# CurrentStabilizer.net
KiCad netlist of a schematic drawn in EAGLE
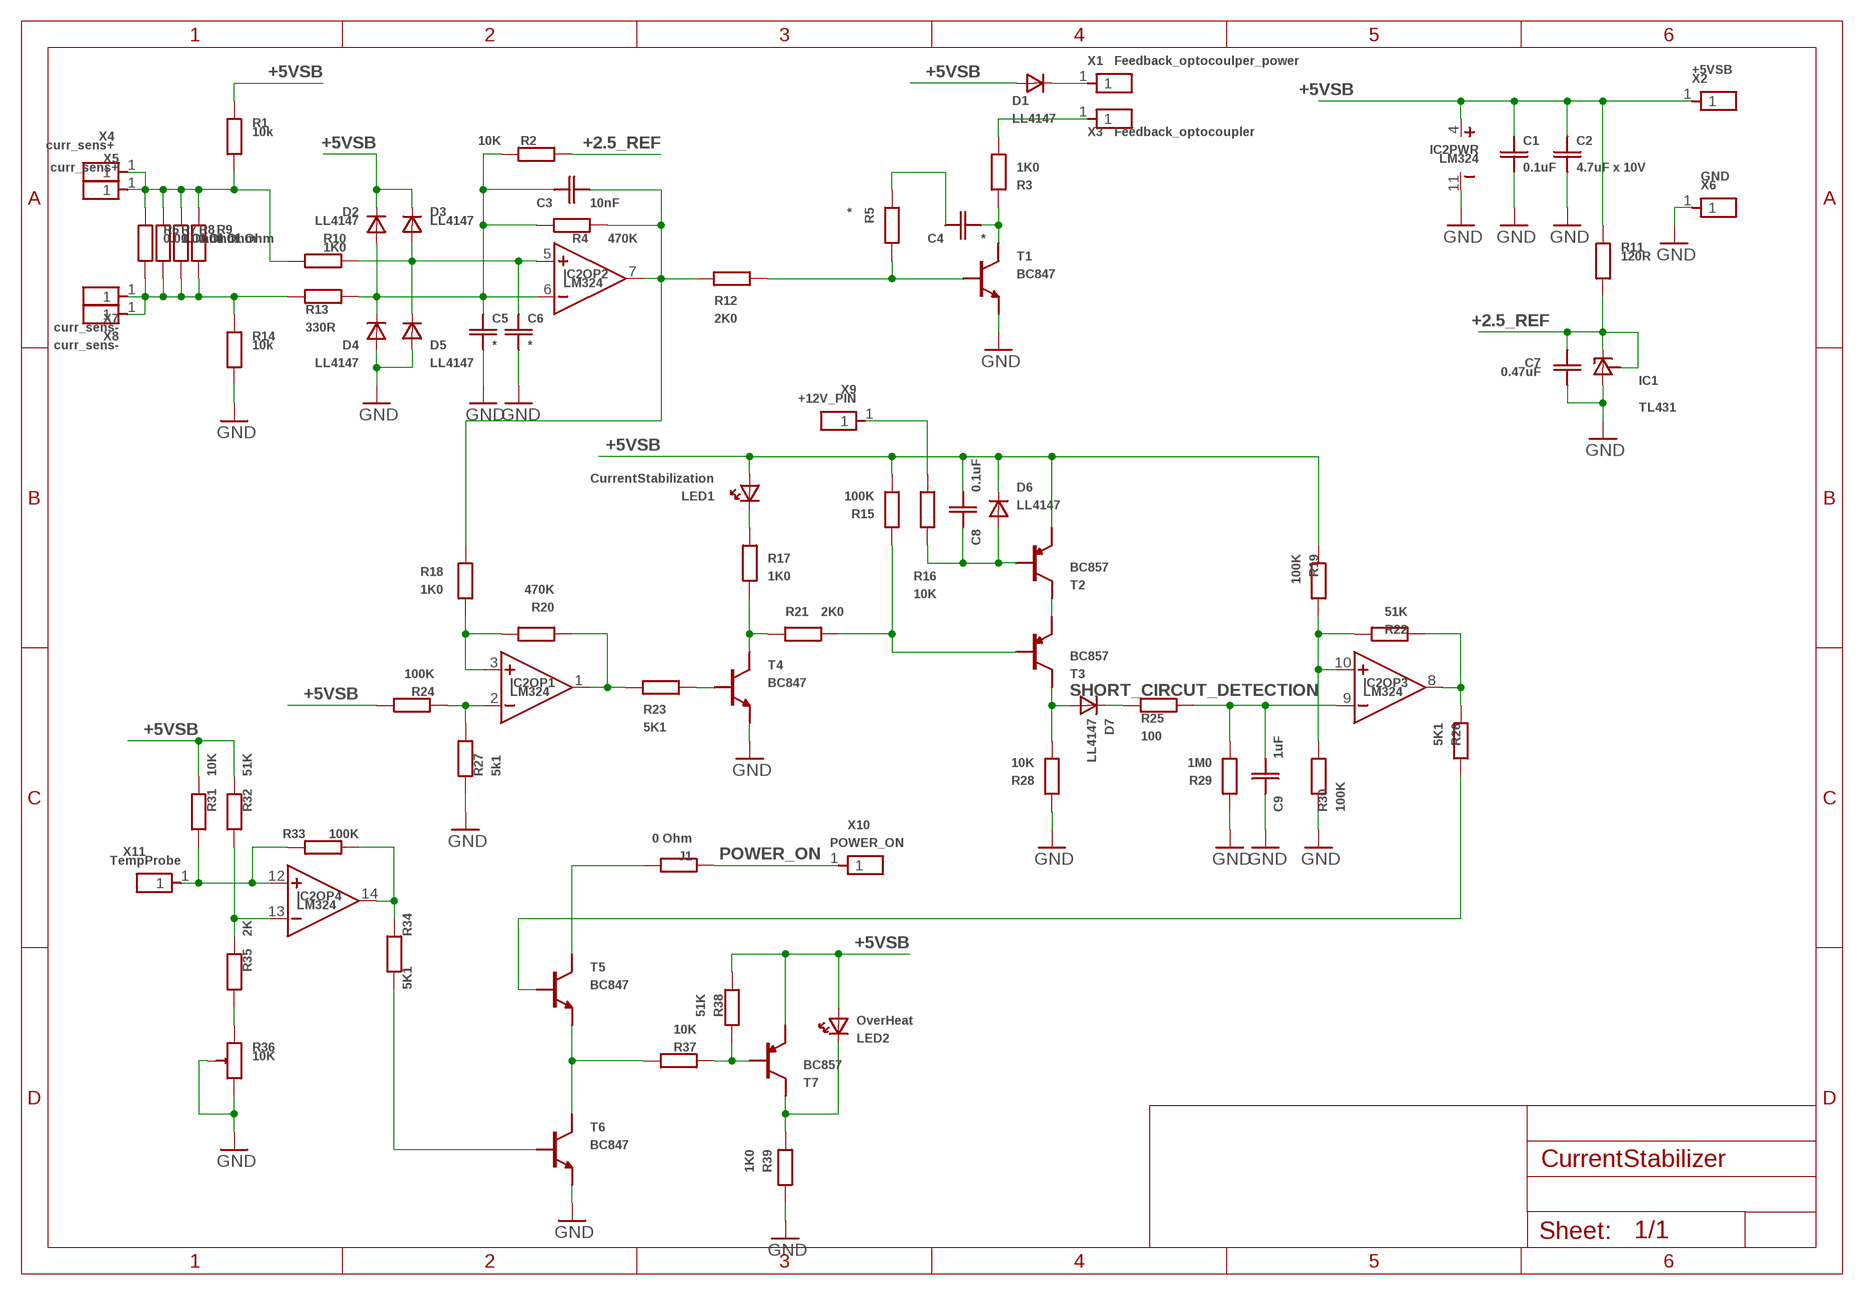
[diagram p0: schematic, sheet 1]

(export (version "E")
  (design (tool "Eeschema 10.0.6"))
  (components
    (comp (ref "C1")
      (value "0.1uF")
      (footprint "eagle-import:RSMD_1206_BIG_GAP")
      (libsource (lib "eagle-import") (part "CSMD_1206_BIG_GAP"))
    )
    (comp (ref "C2")
      (value "4.7uF x 10V")
      (footprint "eagle-import:RSMD_1206")
      (libsource (lib "eagle-import") (part "CSMD_1206"))
    )
    (comp (ref "C3")
      (value "10nF")
      (footprint "eagle-import:RSMD_0805")
      (libsource (lib "eagle-import") (part "CSMD_0805"))
    )
    (comp (ref "C4")
      (value "*")
      (footprint "eagle-import:RSMD_0805")
      (libsource (lib "eagle-import") (part "CSMD_0805"))
    )
    (comp (ref "C5")
      (value "*")
      (footprint "eagle-import:RSMD_0805")
      (libsource (lib "eagle-import") (part "CSMD_0805"))
    )
    (comp (ref "C6")
      (value "*")
      (footprint "eagle-import:RSMD_0805")
      (libsource (lib "eagle-import") (part "CSMD_0805"))
    )
    (comp (ref "C7")
      (value "0.47uF")
      (footprint "eagle-import:RSMD_0805")
      (libsource (lib "eagle-import") (part "CSMD_0805"))
    )
    (comp (ref "C8")
      (value "0.1uF")
      (footprint "eagle-import:RSMD_0805")
      (libsource (lib "eagle-import") (part "CSMD_0805"))
    )
    (comp (ref "C9")
      (value "1uF")
      (footprint "eagle-import:RSMD_0805")
      (libsource (lib "eagle-import") (part "CSMD_0805"))
    )
    (comp (ref "D1")
      (value "LL4147")
      (footprint "eagle-import:SOD-80")
      (libsource (lib "eagle-import") (part "LL4147SOD-80"))
    )
    (comp (ref "D2")
      (value "LL4147")
      (footprint "eagle-import:SOD-80")
      (libsource (lib "eagle-import") (part "LL4147SOD-80"))
    )
    (comp (ref "D3")
      (value "LL4147")
      (footprint "eagle-import:SOD-80")
      (libsource (lib "eagle-import") (part "LL4147SOD-80"))
    )
    (comp (ref "D4")
      (value "LL4147")
      (footprint "eagle-import:SOD-80")
      (libsource (lib "eagle-import") (part "LL4147SOD-80"))
    )
    (comp (ref "D5")
      (value "LL4147")
      (footprint "eagle-import:SOD-80")
      (libsource (lib "eagle-import") (part "LL4147SOD-80"))
    )
    (comp (ref "D6")
      (value "LL4147")
      (footprint "eagle-import:SOD-80")
      (libsource (lib "eagle-import") (part "LL4147SOD-80"))
    )
    (comp (ref "D7")
      (value "LL4147")
      (footprint "eagle-import:SOD-80")
      (libsource (lib "eagle-import") (part "LL4147SOD-80"))
    )
    (comp (ref "IC1")
      (value "TL431")
      (footprint "eagle-import:SOT23")
      (libsource (lib "eagle-import") (part "TL431SOT23"))
    )
    (comp (ref "IC2")
      (value "LM324")
      (footprint "eagle-import:SOIC14")
      (libsource (lib "eagle-import") (part "LM324"))
    )
    (comp (ref "J1")
      (value "0 Ohm")
      (footprint "eagle-import:RSMD_0805")
      (libsource (lib "eagle-import") (part "RSMD_0805"))
    )
    (comp (ref "LED1")
      (value "CurrentStabilization")
      (footprint "eagle-import:LED3MM")
      (libsource (lib "eagle-import") (part "LED3MM"))
    )
    (comp (ref "LED2")
      (value "OverHeat")
      (footprint "eagle-import:LED3MM")
      (libsource (lib "eagle-import") (part "LED3MM"))
    )
    (comp (ref "R1")
      (value "10k")
      (footprint "eagle-import:RSMD_0805")
      (libsource (lib "eagle-import") (part "RSMD_0805"))
    )
    (comp (ref "R2")
      (value "10K")
      (footprint "eagle-import:RSMD_0805")
      (libsource (lib "eagle-import") (part "RSMD_0805"))
    )
    (comp (ref "R3")
      (value "1K0")
      (footprint "eagle-import:RSMD_0805")
      (libsource (lib "eagle-import") (part "RSMD_0805"))
    )
    (comp (ref "R4")
      (value "470K")
      (footprint "eagle-import:RSMD_0805")
      (libsource (lib "eagle-import") (part "RSMD_0805"))
    )
    (comp (ref "R5")
      (value "*")
      (footprint "eagle-import:RSMD_0805")
      (libsource (lib "eagle-import") (part "RSMD_0805"))
    )
    (comp (ref "R6")
      (value "0.01 Ohm")
      (footprint "eagle-import:RSMD_2512")
      (libsource (lib "eagle-import") (part "RSMD_2512"))
    )
    (comp (ref "R7")
      (value "0.01 Ohm")
      (footprint "eagle-import:RSMD_2512")
      (libsource (lib "eagle-import") (part "RSMD_2512"))
    )
    (comp (ref "R8")
      (value "0.01 Ohm")
      (footprint "eagle-import:RSMD_2512")
      (libsource (lib "eagle-import") (part "RSMD_2512"))
    )
    (comp (ref "R9")
      (value "0.01 Ohm")
      (footprint "eagle-import:RSMD_2512")
      (libsource (lib "eagle-import") (part "RSMD_2512"))
    )
    (comp (ref "R10")
      (value "1K0")
      (footprint "eagle-import:RSMD_0805")
      (libsource (lib "eagle-import") (part "RSMD_0805"))
    )
    (comp (ref "R11")
      (value "120R")
      (footprint "eagle-import:RSMD_0805")
      (libsource (lib "eagle-import") (part "RSMD_0805"))
    )
    (comp (ref "R12")
      (value "2K0")
      (footprint "eagle-import:RSMD_0805")
      (libsource (lib "eagle-import") (part "RSMD_0805"))
    )
    (comp (ref "R13")
      (value "330R")
      (footprint "eagle-import:RSMD_0805")
      (libsource (lib "eagle-import") (part "RSMD_0805"))
    )
    (comp (ref "R14")
      (value "10k")
      (footprint "eagle-import:RSMD_0805")
      (libsource (lib "eagle-import") (part "RSMD_0805"))
    )
    (comp (ref "R15")
      (value "100K")
      (footprint "eagle-import:RSMD_0805")
      (libsource (lib "eagle-import") (part "RSMD_0805"))
    )
    (comp (ref "R16")
      (value "10K")
      (footprint "eagle-import:RSMD_0805")
      (libsource (lib "eagle-import") (part "RSMD_0805"))
    )
    (comp (ref "R17")
      (value "1K0")
      (footprint "eagle-import:RSMD_0805")
      (libsource (lib "eagle-import") (part "RSMD_0805"))
    )
    (comp (ref "R18")
      (value "1K0")
      (footprint "eagle-import:RSMD_0805")
      (libsource (lib "eagle-import") (part "RSMD_0805"))
    )
    (comp (ref "R19")
      (value "100K")
      (footprint "eagle-import:RSMD_0805")
      (libsource (lib "eagle-import") (part "RSMD_0805"))
    )
    (comp (ref "R20")
      (value "470K")
      (footprint "eagle-import:RSMD_0805")
      (libsource (lib "eagle-import") (part "RSMD_0805"))
    )
    (comp (ref "R21")
      (value "2K0")
      (footprint "eagle-import:RSMD_0805")
      (libsource (lib "eagle-import") (part "RSMD_0805"))
    )
    (comp (ref "R22")
      (value "51K")
      (footprint "eagle-import:RSMD_0805")
      (libsource (lib "eagle-import") (part "RSMD_0805"))
    )
    (comp (ref "R23")
      (value "5K1")
      (footprint "eagle-import:RSMD_0805")
      (libsource (lib "eagle-import") (part "RSMD_0805"))
    )
    (comp (ref "R24")
      (value "100K")
      (footprint "eagle-import:RSMD_0805")
      (libsource (lib "eagle-import") (part "RSMD_0805"))
    )
    (comp (ref "R25")
      (value "100")
      (footprint "eagle-import:RSMD_0805")
      (libsource (lib "eagle-import") (part "RSMD_0805"))
    )
    (comp (ref "R26")
      (value "5K1")
      (footprint "eagle-import:RSMD_0805")
      (libsource (lib "eagle-import") (part "RSMD_0805"))
    )
    (comp (ref "R27")
      (value "5k1")
      (footprint "eagle-import:RSMD_0805")
      (libsource (lib "eagle-import") (part "RSMD_0805"))
    )
    (comp (ref "R28")
      (value "10K")
      (footprint "eagle-import:RSMD_0805")
      (libsource (lib "eagle-import") (part "RSMD_0805"))
    )
    (comp (ref "R29")
      (value "1M0")
      (footprint "eagle-import:RSMD_0805")
      (libsource (lib "eagle-import") (part "RSMD_0805"))
    )
    (comp (ref "R30")
      (value "100K")
      (footprint "eagle-import:RSMD_0805")
      (libsource (lib "eagle-import") (part "RSMD_0805"))
    )
    (comp (ref "R31")
      (value "10K")
      (footprint "eagle-import:RSMD_0805")
      (libsource (lib "eagle-import") (part "RSMD_0805"))
    )
    (comp (ref "R32")
      (value "51K")
      (footprint "eagle-import:RSMD_0805")
      (libsource (lib "eagle-import") (part "RSMD_0805"))
    )
    (comp (ref "R33")
      (value "100K")
      (footprint "eagle-import:RSMD_0805")
      (libsource (lib "eagle-import") (part "RSMD_0805"))
    )
    (comp (ref "R34")
      (value "5K1")
      (footprint "eagle-import:RSMD_0805")
      (libsource (lib "eagle-import") (part "RSMD_0805"))
    )
    (comp (ref "R35")
      (value "2K")
      (footprint "eagle-import:RSMD_0805")
      (libsource (lib "eagle-import") (part "RSMD_0805"))
    )
    (comp (ref "R36")
      (value "10K")
      (footprint "eagle-import:R_ADJ_STAND")
      (libsource (lib "eagle-import") (part "R_ADJSTAND_6.5_X_3.5MM"))
    )
    (comp (ref "R37")
      (value "10K")
      (footprint "eagle-import:RSMD_0805")
      (libsource (lib "eagle-import") (part "RSMD_0805"))
    )
    (comp (ref "R38")
      (value "51K")
      (footprint "eagle-import:RSMD_0805")
      (libsource (lib "eagle-import") (part "RSMD_0805"))
    )
    (comp (ref "R39")
      (value "1K0")
      (footprint "eagle-import:RSMD_1206")
      (libsource (lib "eagle-import") (part "RSMD_1206"))
    )
    (comp (ref "T1")
      (value "BC847")
      (footprint "eagle-import:SOT23_SMALL_PADS")
      (libsource (lib "eagle-import") (part "BC847SOT23_SMALL_PADS"))
    )
    (comp (ref "T2")
      (value "BC857")
      (footprint "eagle-import:SOT23_SMALL_PADS")
      (libsource (lib "eagle-import") (part "BC857SOT23_SMALL_PADS"))
    )
    (comp (ref "T3")
      (value "BC857")
      (footprint "eagle-import:SOT23_SMALL_PADS")
      (libsource (lib "eagle-import") (part "BC857SOT23_SMALL_PADS"))
    )
    (comp (ref "T4")
      (value "BC847")
      (footprint "eagle-import:SOT23_SMALL_PADS")
      (libsource (lib "eagle-import") (part "BC847SOT23_SMALL_PADS"))
    )
    (comp (ref "T5")
      (value "BC847")
      (footprint "eagle-import:SOT23_SMALL_PADS")
      (libsource (lib "eagle-import") (part "BC847SOT23_SMALL_PADS"))
    )
    (comp (ref "T6")
      (value "BC847")
      (footprint "eagle-import:SOT23_SMALL_PADS")
      (libsource (lib "eagle-import") (part "BC847SOT23_SMALL_PADS"))
    )
    (comp (ref "T7")
      (value "BC857")
      (footprint "eagle-import:SOT23_SMALL_PADS")
      (libsource (lib "eagle-import") (part "BC857SOT23_SMALL_PADS"))
    )
    (comp (ref "X1")
      (value "Feedback_optocoulper_power")
      (footprint "eagle-import:PIN1X1_2.54MM")
      (libsource (lib "eagle-import") (part "PIN1X12.54MM"))
    )
    (comp (ref "X2")
      (value "+5VSB")
      (footprint "eagle-import:PIN1X1_2.54MM")
      (libsource (lib "eagle-import") (part "PIN1X12.54MM"))
    )
    (comp (ref "X3")
      (value "Feedback_optocoupler")
      (footprint "eagle-import:PIN1X1_2.54MM")
      (libsource (lib "eagle-import") (part "PIN1X12.54MM"))
    )
    (comp (ref "X4")
      (value "curr_sens+")
      (footprint "eagle-import:PIN1X1_2.54MM")
      (libsource (lib "eagle-import") (part "PIN1X12.54MM"))
    )
    (comp (ref "X5")
      (value "curr_sens+")
      (footprint "eagle-import:PIN1X1_2.54MM")
      (libsource (lib "eagle-import") (part "PIN1X12.54MM"))
    )
    (comp (ref "X6")
      (value "GND")
      (footprint "eagle-import:PIN1X1_2.54MM")
      (libsource (lib "eagle-import") (part "PIN1X12.54MM"))
    )
    (comp (ref "X7")
      (value "curr_sens-")
      (footprint "eagle-import:PIN1X1_2.54MM")
      (libsource (lib "eagle-import") (part "PIN1X12.54MM"))
    )
    (comp (ref "X8")
      (value "curr_sens-")
      (footprint "eagle-import:PIN1X1_2.54MM")
      (libsource (lib "eagle-import") (part "PIN1X12.54MM"))
    )
    (comp (ref "X9")
      (value "+12V_PIN")
      (footprint "eagle-import:PIN1X1_2.54MM")
      (libsource (lib "eagle-import") (part "PIN1X12.54MM"))
    )
    (comp (ref "X10")
      (value "POWER_ON")
      (footprint "eagle-import:PIN1X1_2.54MM")
      (libsource (lib "eagle-import") (part "PIN1X12.54MM"))
    )
    (comp (ref "X11")
      (value "TempProbe")
      (footprint "eagle-import:PIN1X1_2.54MM")
      (libsource (lib "eagle-import") (part "PIN1X12.54MM"))
    )
  )
  (nets
    (net (code "1") (name "/+2.5_REF") (class "Default")
      (node (ref "C7") (pin "PAD_1") (pinfunction "PIN1_PAD_1") (pintype "bidirectional"))
      (node (ref "IC1") (pin "1") (pinfunction "CATHODE_1") (pintype "passive"))
      (node (ref "IC1") (pin "2") (pinfunction "REFERENCE_2") (pintype "passive"))
      (node (ref "R11") (pin "PAD_0") (pinfunction "PIN0_PAD_0") (pintype "passive"))
      (node (ref "R2") (pin "PAD_0") (pinfunction "PIN0_PAD_0") (pintype "passive"))
    )
    (net (code "2") (name "/+5VSB") (class "Default")
      (node (ref "C1") (pin "PAD_1") (pinfunction "PIN1_PAD_1") (pintype "bidirectional"))
      (node (ref "C2") (pin "PAD_1") (pinfunction "PIN1_PAD_1") (pintype "bidirectional"))
      (node (ref "C8") (pin "PAD_0") (pinfunction "PIN0_PAD_0") (pintype "bidirectional"))
      (node (ref "D1") (pin "ANODE") (pinfunction "ANODE_ANODE") (pintype "passive"))
      (node (ref "D2") (pin "CATHODE") (pinfunction "CATHODE_CATHODE") (pintype "passive"))
      (node (ref "D3") (pin "CATHODE") (pinfunction "CATHODE_CATHODE") (pintype "passive"))
      (node (ref "D6") (pin "CATHODE") (pinfunction "CATHODE_CATHODE") (pintype "passive"))
      (node (ref "IC2") (pin "4") (pinfunction "VCC_4") (pintype "power_in"))
      (node (ref "LED1") (pin "ANODE") (pinfunction "ANODE_ANODE") (pintype "passive"))
      (node (ref "LED2") (pin "ANODE") (pinfunction "ANODE_ANODE") (pintype "passive"))
      (node (ref "R1") (pin "PAD_1") (pinfunction "PIN1_PAD_1") (pintype "passive"))
      (node (ref "R11") (pin "PAD_1") (pinfunction "PIN1_PAD_1") (pintype "passive"))
      (node (ref "R15") (pin "PAD_0") (pinfunction "PIN0_PAD_0") (pintype "passive"))
      (node (ref "R19") (pin "PAD_0") (pinfunction "PIN0_PAD_0") (pintype "passive"))
      (node (ref "R24") (pin "PAD_1") (pinfunction "PIN1_PAD_1") (pintype "passive"))
      (node (ref "R31") (pin "PAD_1") (pinfunction "PIN1_PAD_1") (pintype "passive"))
      (node (ref "R32") (pin "PAD_1") (pinfunction "PIN1_PAD_1") (pintype "passive"))
      (node (ref "R38") (pin "PAD_0") (pinfunction "PIN0_PAD_0") (pintype "passive"))
      (node (ref "T2") (pin "2") (pinfunction "E_2") (pintype "bidirectional"))
      (node (ref "T7") (pin "2") (pinfunction "E_2") (pintype "bidirectional"))
      (node (ref "X2") (pin "1") (pinfunction "1_1") (pintype "bidirectional"))
    )
    (net (code "3") (name "/POWER_ON") (class "Default")
      (node (ref "J1") (pin "PAD_0") (pinfunction "PIN0_PAD_0") (pintype "passive"))
      (node (ref "X10") (pin "1") (pinfunction "1_1") (pintype "bidirectional"))
    )
    (net (code "4") (name "/SHORT_CIRCUT_DETECTION") (class "Default")
      (node (ref "D7") (pin "ANODE") (pinfunction "ANODE_ANODE") (pintype "passive"))
      (node (ref "R28") (pin "PAD_0") (pinfunction "PIN0_PAD_0") (pintype "passive"))
      (node (ref "T3") (pin "3") (pinfunction "C_3") (pintype "bidirectional"))
    )
    (net (code "5") (name "GND") (class "Default")
      (node (ref "C1") (pin "PAD_0") (pinfunction "PIN0_PAD_0") (pintype "bidirectional"))
      (node (ref "C2") (pin "PAD_0") (pinfunction "PIN0_PAD_0") (pintype "bidirectional"))
      (node (ref "C5") (pin "PAD_0") (pinfunction "PIN0_PAD_0") (pintype "bidirectional"))
      (node (ref "C6") (pin "PAD_0") (pinfunction "PIN0_PAD_0") (pintype "bidirectional"))
      (node (ref "C7") (pin "PAD_0") (pinfunction "PIN0_PAD_0") (pintype "bidirectional"))
      (node (ref "C9") (pin "PAD_1") (pinfunction "PIN1_PAD_1") (pintype "bidirectional"))
      (node (ref "D4") (pin "ANODE") (pinfunction "ANODE_ANODE") (pintype "passive"))
      (node (ref "D5") (pin "ANODE") (pinfunction "ANODE_ANODE") (pintype "passive"))
      (node (ref "IC1") (pin "3") (pinfunction "ANODE_3") (pintype "passive"))
      (node (ref "IC2") (pin "11") (pinfunction "GND_11") (pintype "power_in"))
      (node (ref "R14") (pin "PAD_0") (pinfunction "PIN0_PAD_0") (pintype "passive"))
      (node (ref "R27") (pin "PAD_0") (pinfunction "PIN0_PAD_0") (pintype "passive"))
      (node (ref "R28") (pin "PAD_1") (pinfunction "PIN1_PAD_1") (pintype "passive"))
      (node (ref "R29") (pin "PAD_1") (pinfunction "PIN1_PAD_1") (pintype "passive"))
      (node (ref "R30") (pin "PAD_0") (pinfunction "PIN0_PAD_0") (pintype "passive"))
      (node (ref "R36") (pin "2") (pinfunction "ADJ_2") (pintype "passive"))
      (node (ref "R36") (pin "3") (pinfunction "END_B_3") (pintype "passive"))
      (node (ref "R39") (pin "PAD_1") (pinfunction "PIN1_PAD_1") (pintype "passive"))
      (node (ref "T1") (pin "2") (pinfunction "E_2") (pintype "bidirectional"))
      (node (ref "T4") (pin "2") (pinfunction "E_2") (pintype "bidirectional"))
      (node (ref "T6") (pin "2") (pinfunction "E_2") (pintype "bidirectional"))
      (node (ref "X6") (pin "1") (pinfunction "1_1") (pintype "bidirectional"))
    )
    (net (code "6") (name "Net-(C3-PIN0)") (class "Default")
      (node (ref "C3") (pin "PAD_0") (pinfunction "PIN0_PAD_0") (pintype "bidirectional"))
      (node (ref "IC2") (pin "7") (pinfunction "OUT_7") (pintype "output"))
      (node (ref "R12") (pin "PAD_1") (pinfunction "PIN1_PAD_1") (pintype "passive"))
      (node (ref "R18") (pin "PAD_1") (pinfunction "PIN1_PAD_1") (pintype "passive"))
      (node (ref "R4") (pin "PAD_1") (pinfunction "PIN1_PAD_1") (pintype "passive"))
    )
    (net (code "7") (name "Net-(C3-PIN1)") (class "Default")
      (node (ref "C3") (pin "PAD_1") (pinfunction "PIN1_PAD_1") (pintype "bidirectional"))
      (node (ref "C5") (pin "PAD_1") (pinfunction "PIN1_PAD_1") (pintype "bidirectional"))
      (node (ref "D2") (pin "ANODE") (pinfunction "ANODE_ANODE") (pintype "passive"))
      (node (ref "D4") (pin "CATHODE") (pinfunction "CATHODE_CATHODE") (pintype "passive"))
      (node (ref "IC2") (pin "6") (pinfunction "IN-_6") (pintype "input"))
      (node (ref "R13") (pin "PAD_1") (pinfunction "PIN1_PAD_1") (pintype "passive"))
      (node (ref "R2") (pin "PAD_1") (pinfunction "PIN1_PAD_1") (pintype "passive"))
      (node (ref "R4") (pin "PAD_0") (pinfunction "PIN0_PAD_0") (pintype "passive"))
    )
    (net (code "8") (name "Net-(C4-PIN0)") (class "Default")
      (node (ref "C4") (pin "PAD_0") (pinfunction "PIN0_PAD_0") (pintype "bidirectional"))
      (node (ref "R3") (pin "PAD_0") (pinfunction "PIN0_PAD_0") (pintype "passive"))
      (node (ref "T1") (pin "3") (pinfunction "C_3") (pintype "bidirectional"))
    )
    (net (code "9") (name "Net-(C4-PIN1)") (class "Default")
      (node (ref "C4") (pin "PAD_1") (pinfunction "PIN1_PAD_1") (pintype "bidirectional"))
      (node (ref "R5") (pin "PAD_1") (pinfunction "PIN1_PAD_1") (pintype "passive"))
    )
    (net (code "10") (name "Net-(C6-PIN1)") (class "Default")
      (node (ref "C6") (pin "PAD_1") (pinfunction "PIN1_PAD_1") (pintype "bidirectional"))
      (node (ref "D3") (pin "ANODE") (pinfunction "ANODE_ANODE") (pintype "passive"))
      (node (ref "D5") (pin "CATHODE") (pinfunction "CATHODE_CATHODE") (pintype "passive"))
      (node (ref "IC2") (pin "5") (pinfunction "IN+_5") (pintype "input"))
      (node (ref "R10") (pin "PAD_1") (pinfunction "PIN1_PAD_1") (pintype "passive"))
    )
    (net (code "11") (name "Net-(C8-PIN1)") (class "Default")
      (node (ref "C8") (pin "PAD_1") (pinfunction "PIN1_PAD_1") (pintype "bidirectional"))
      (node (ref "D6") (pin "ANODE") (pinfunction "ANODE_ANODE") (pintype "passive"))
      (node (ref "R16") (pin "PAD_1") (pinfunction "PIN1_PAD_1") (pintype "passive"))
      (node (ref "T2") (pin "1") (pinfunction "B_1") (pintype "bidirectional"))
    )
    (net (code "12") (name "Net-(C9-PIN0)") (class "Default")
      (node (ref "C9") (pin "PAD_0") (pinfunction "PIN0_PAD_0") (pintype "bidirectional"))
      (node (ref "IC2") (pin "9") (pinfunction "IN-_9") (pintype "input"))
      (node (ref "R25") (pin "PAD_1") (pinfunction "PIN1_PAD_1") (pintype "passive"))
      (node (ref "R29") (pin "PAD_0") (pinfunction "PIN0_PAD_0") (pintype "passive"))
    )
    (net (code "13") (name "Net-(D1-PadCATHODE)") (class "Default")
      (node (ref "D1") (pin "CATHODE") (pinfunction "CATHODE_CATHODE") (pintype "passive"))
      (node (ref "X1") (pin "1") (pinfunction "1_1") (pintype "bidirectional"))
    )
    (net (code "14") (name "Net-(IC2A-IN+)") (class "Default")
      (node (ref "IC2") (pin "3") (pinfunction "IN+_3") (pintype "input"))
      (node (ref "R18") (pin "PAD_0") (pinfunction "PIN0_PAD_0") (pintype "passive"))
      (node (ref "R20") (pin "PAD_0") (pinfunction "PIN0_PAD_0") (pintype "passive"))
    )
    (net (code "15") (name "Net-(IC2A-IN-)") (class "Default")
      (node (ref "IC2") (pin "2") (pinfunction "IN-_2") (pintype "input"))
      (node (ref "R24") (pin "PAD_0") (pinfunction "PIN0_PAD_0") (pintype "passive"))
      (node (ref "R27") (pin "PAD_1") (pinfunction "PIN1_PAD_1") (pintype "passive"))
    )
    (net (code "16") (name "Net-(IC2A-OUT)") (class "Default")
      (node (ref "IC2") (pin "1") (pinfunction "OUT_1") (pintype "output"))
      (node (ref "R20") (pin "PAD_1") (pinfunction "PIN1_PAD_1") (pintype "passive"))
      (node (ref "R23") (pin "PAD_1") (pinfunction "PIN1_PAD_1") (pintype "passive"))
    )
    (net (code "17") (name "Net-(IC2C-IN+)") (class "Default")
      (node (ref "IC2") (pin "10") (pinfunction "IN+_10") (pintype "input"))
      (node (ref "R19") (pin "PAD_1") (pinfunction "PIN1_PAD_1") (pintype "passive"))
      (node (ref "R22") (pin "PAD_1") (pinfunction "PIN1_PAD_1") (pintype "passive"))
      (node (ref "R30") (pin "PAD_1") (pinfunction "PIN1_PAD_1") (pintype "passive"))
    )
    (net (code "18") (name "Net-(IC2C-OUT)") (class "Default")
      (node (ref "IC2") (pin "8") (pinfunction "OUT_8") (pintype "output"))
      (node (ref "R22") (pin "PAD_0") (pinfunction "PIN0_PAD_0") (pintype "passive"))
      (node (ref "R26") (pin "PAD_0") (pinfunction "PIN0_PAD_0") (pintype "passive"))
    )
    (net (code "19") (name "Net-(IC2D-IN+)") (class "Default")
      (node (ref "IC2") (pin "12") (pinfunction "IN+_12") (pintype "input"))
      (node (ref "R31") (pin "PAD_0") (pinfunction "PIN0_PAD_0") (pintype "passive"))
      (node (ref "R33") (pin "PAD_1") (pinfunction "PIN1_PAD_1") (pintype "passive"))
      (node (ref "X11") (pin "1") (pinfunction "1_1") (pintype "bidirectional"))
    )
    (net (code "20") (name "Net-(IC2D-IN-)") (class "Default")
      (node (ref "IC2") (pin "13") (pinfunction "IN-_13") (pintype "input"))
      (node (ref "R32") (pin "PAD_0") (pinfunction "PIN0_PAD_0") (pintype "passive"))
      (node (ref "R35") (pin "PAD_1") (pinfunction "PIN1_PAD_1") (pintype "passive"))
    )
    (net (code "21") (name "Net-(IC2D-OUT)") (class "Default")
      (node (ref "IC2") (pin "14") (pinfunction "OUT_14") (pintype "output"))
      (node (ref "R33") (pin "PAD_0") (pinfunction "PIN0_PAD_0") (pintype "passive"))
      (node (ref "R34") (pin "PAD_1") (pinfunction "PIN1_PAD_1") (pintype "passive"))
    )
    (net (code "22") (name "Net-(J1-PIN1)") (class "Default")
      (node (ref "J1") (pin "PAD_1") (pinfunction "PIN1_PAD_1") (pintype "passive"))
      (node (ref "T5") (pin "3") (pinfunction "C_3") (pintype "bidirectional"))
    )
    (net (code "23") (name "Net-(R1-PIN0)") (class "Default")
      (node (ref "R1") (pin "PAD_0") (pinfunction "PIN0_PAD_0") (pintype "passive"))
      (node (ref "R10") (pin "PAD_0") (pinfunction "PIN0_PAD_0") (pintype "passive"))
      (node (ref "R6") (pin "PAD1") (pinfunction "PIN1_PAD1") (pintype "passive"))
      (node (ref "R7") (pin "PAD1") (pinfunction "PIN1_PAD1") (pintype "passive"))
      (node (ref "R8") (pin "PAD1") (pinfunction "PIN1_PAD1") (pintype "passive"))
      (node (ref "R9") (pin "PAD1") (pinfunction "PIN1_PAD1") (pintype "passive"))
      (node (ref "X4") (pin "1") (pinfunction "1_1") (pintype "bidirectional"))
      (node (ref "X5") (pin "1") (pinfunction "1_1") (pintype "bidirectional"))
    )
    (net (code "24") (name "Net-(R3-PIN1)") (class "Default")
      (node (ref "R3") (pin "PAD_1") (pinfunction "PIN1_PAD_1") (pintype "passive"))
      (node (ref "X3") (pin "1") (pinfunction "1_1") (pintype "bidirectional"))
    )
    (net (code "25") (name "Net-(R12-PIN0)") (class "Default")
      (node (ref "R12") (pin "PAD_0") (pinfunction "PIN0_PAD_0") (pintype "passive"))
      (node (ref "R5") (pin "PAD_0") (pinfunction "PIN0_PAD_0") (pintype "passive"))
      (node (ref "T1") (pin "1") (pinfunction "B_1") (pintype "bidirectional"))
    )
    (net (code "26") (name "Net-(R13-PIN0)") (class "Default")
      (node (ref "R13") (pin "PAD_0") (pinfunction "PIN0_PAD_0") (pintype "passive"))
      (node (ref "R14") (pin "PAD_1") (pinfunction "PIN1_PAD_1") (pintype "passive"))
      (node (ref "R6") (pin "PAD0") (pinfunction "PIN0_PAD0") (pintype "passive"))
      (node (ref "R7") (pin "PAD0") (pinfunction "PIN0_PAD0") (pintype "passive"))
      (node (ref "R8") (pin "PAD0") (pinfunction "PIN0_PAD0") (pintype "passive"))
      (node (ref "R9") (pin "PAD0") (pinfunction "PIN0_PAD0") (pintype "passive"))
      (node (ref "X7") (pin "1") (pinfunction "1_1") (pintype "bidirectional"))
      (node (ref "X8") (pin "1") (pinfunction "1_1") (pintype "bidirectional"))
    )
    (net (code "27") (name "Net-(R15-PIN1)") (class "Default")
      (node (ref "R15") (pin "PAD_1") (pinfunction "PIN1_PAD_1") (pintype "passive"))
      (node (ref "R21") (pin "PAD_1") (pinfunction "PIN1_PAD_1") (pintype "passive"))
      (node (ref "T3") (pin "1") (pinfunction "B_1") (pintype "bidirectional"))
    )
    (net (code "28") (name "Net-(R16-PIN0)") (class "Default")
      (node (ref "R16") (pin "PAD_0") (pinfunction "PIN0_PAD_0") (pintype "passive"))
      (node (ref "X9") (pin "1") (pinfunction "1_1") (pintype "bidirectional"))
    )
    (net (code "29") (name "Net-(R17-PIN0)") (class "Default")
      (node (ref "LED1") (pin "CATHODE") (pinfunction "CATHODE_CATHODE") (pintype "passive"))
      (node (ref "R17") (pin "PAD_0") (pinfunction "PIN0_PAD_0") (pintype "passive"))
    )
    (net (code "30") (name "Net-(R17-PIN1)") (class "Default")
      (node (ref "R17") (pin "PAD_1") (pinfunction "PIN1_PAD_1") (pintype "passive"))
      (node (ref "R21") (pin "PAD_0") (pinfunction "PIN0_PAD_0") (pintype "passive"))
      (node (ref "T4") (pin "3") (pinfunction "C_3") (pintype "bidirectional"))
    )
    (net (code "31") (name "Net-(R23-PIN0)") (class "Default")
      (node (ref "R23") (pin "PAD_0") (pinfunction "PIN0_PAD_0") (pintype "passive"))
      (node (ref "T4") (pin "1") (pinfunction "B_1") (pintype "bidirectional"))
    )
    (net (code "32") (name "Net-(R25-PIN0)") (class "Default")
      (node (ref "D7") (pin "CATHODE") (pinfunction "CATHODE_CATHODE") (pintype "passive"))
      (node (ref "R25") (pin "PAD_0") (pinfunction "PIN0_PAD_0") (pintype "passive"))
    )
    (net (code "33") (name "Net-(R26-PIN1)") (class "Default")
      (node (ref "R26") (pin "PAD_1") (pinfunction "PIN1_PAD_1") (pintype "passive"))
      (node (ref "T5") (pin "1") (pinfunction "B_1") (pintype "bidirectional"))
    )
    (net (code "34") (name "Net-(R34-PIN0)") (class "Default")
      (node (ref "R34") (pin "PAD_0") (pinfunction "PIN0_PAD_0") (pintype "passive"))
      (node (ref "T6") (pin "1") (pinfunction "B_1") (pintype "bidirectional"))
    )
    (net (code "35") (name "Net-(R35-PIN0)") (class "Default")
      (node (ref "R35") (pin "PAD_0") (pinfunction "PIN0_PAD_0") (pintype "passive"))
      (node (ref "R36") (pin "1") (pinfunction "END_A_1") (pintype "passive"))
    )
    (net (code "36") (name "Net-(R37-PIN0)") (class "Default")
      (node (ref "R37") (pin "PAD_0") (pinfunction "PIN0_PAD_0") (pintype "passive"))
      (node (ref "R38") (pin "PAD_1") (pinfunction "PIN1_PAD_1") (pintype "passive"))
      (node (ref "T7") (pin "1") (pinfunction "B_1") (pintype "bidirectional"))
    )
    (net (code "37") (name "Net-(R37-PIN1)") (class "Default")
      (node (ref "R37") (pin "PAD_1") (pinfunction "PIN1_PAD_1") (pintype "passive"))
      (node (ref "T5") (pin "2") (pinfunction "E_2") (pintype "bidirectional"))
      (node (ref "T6") (pin "3") (pinfunction "C_3") (pintype "bidirectional"))
    )
    (net (code "38") (name "Net-(R39-PIN0)") (class "Default")
      (node (ref "LED2") (pin "CATHODE") (pinfunction "CATHODE_CATHODE") (pintype "passive"))
      (node (ref "R39") (pin "PAD_0") (pinfunction "PIN0_PAD_0") (pintype "passive"))
      (node (ref "T7") (pin "3") (pinfunction "C_3") (pintype "bidirectional"))
    )
    (net (code "39") (name "Net-(T2-C)") (class "Default")
      (node (ref "T2") (pin "3") (pinfunction "C_3") (pintype "bidirectional"))
      (node (ref "T3") (pin "2") (pinfunction "E_2") (pintype "bidirectional"))
    )
  )
)
